# FT2328Breakout.net
KiCad netlist of a schematic drawn in EAGLE
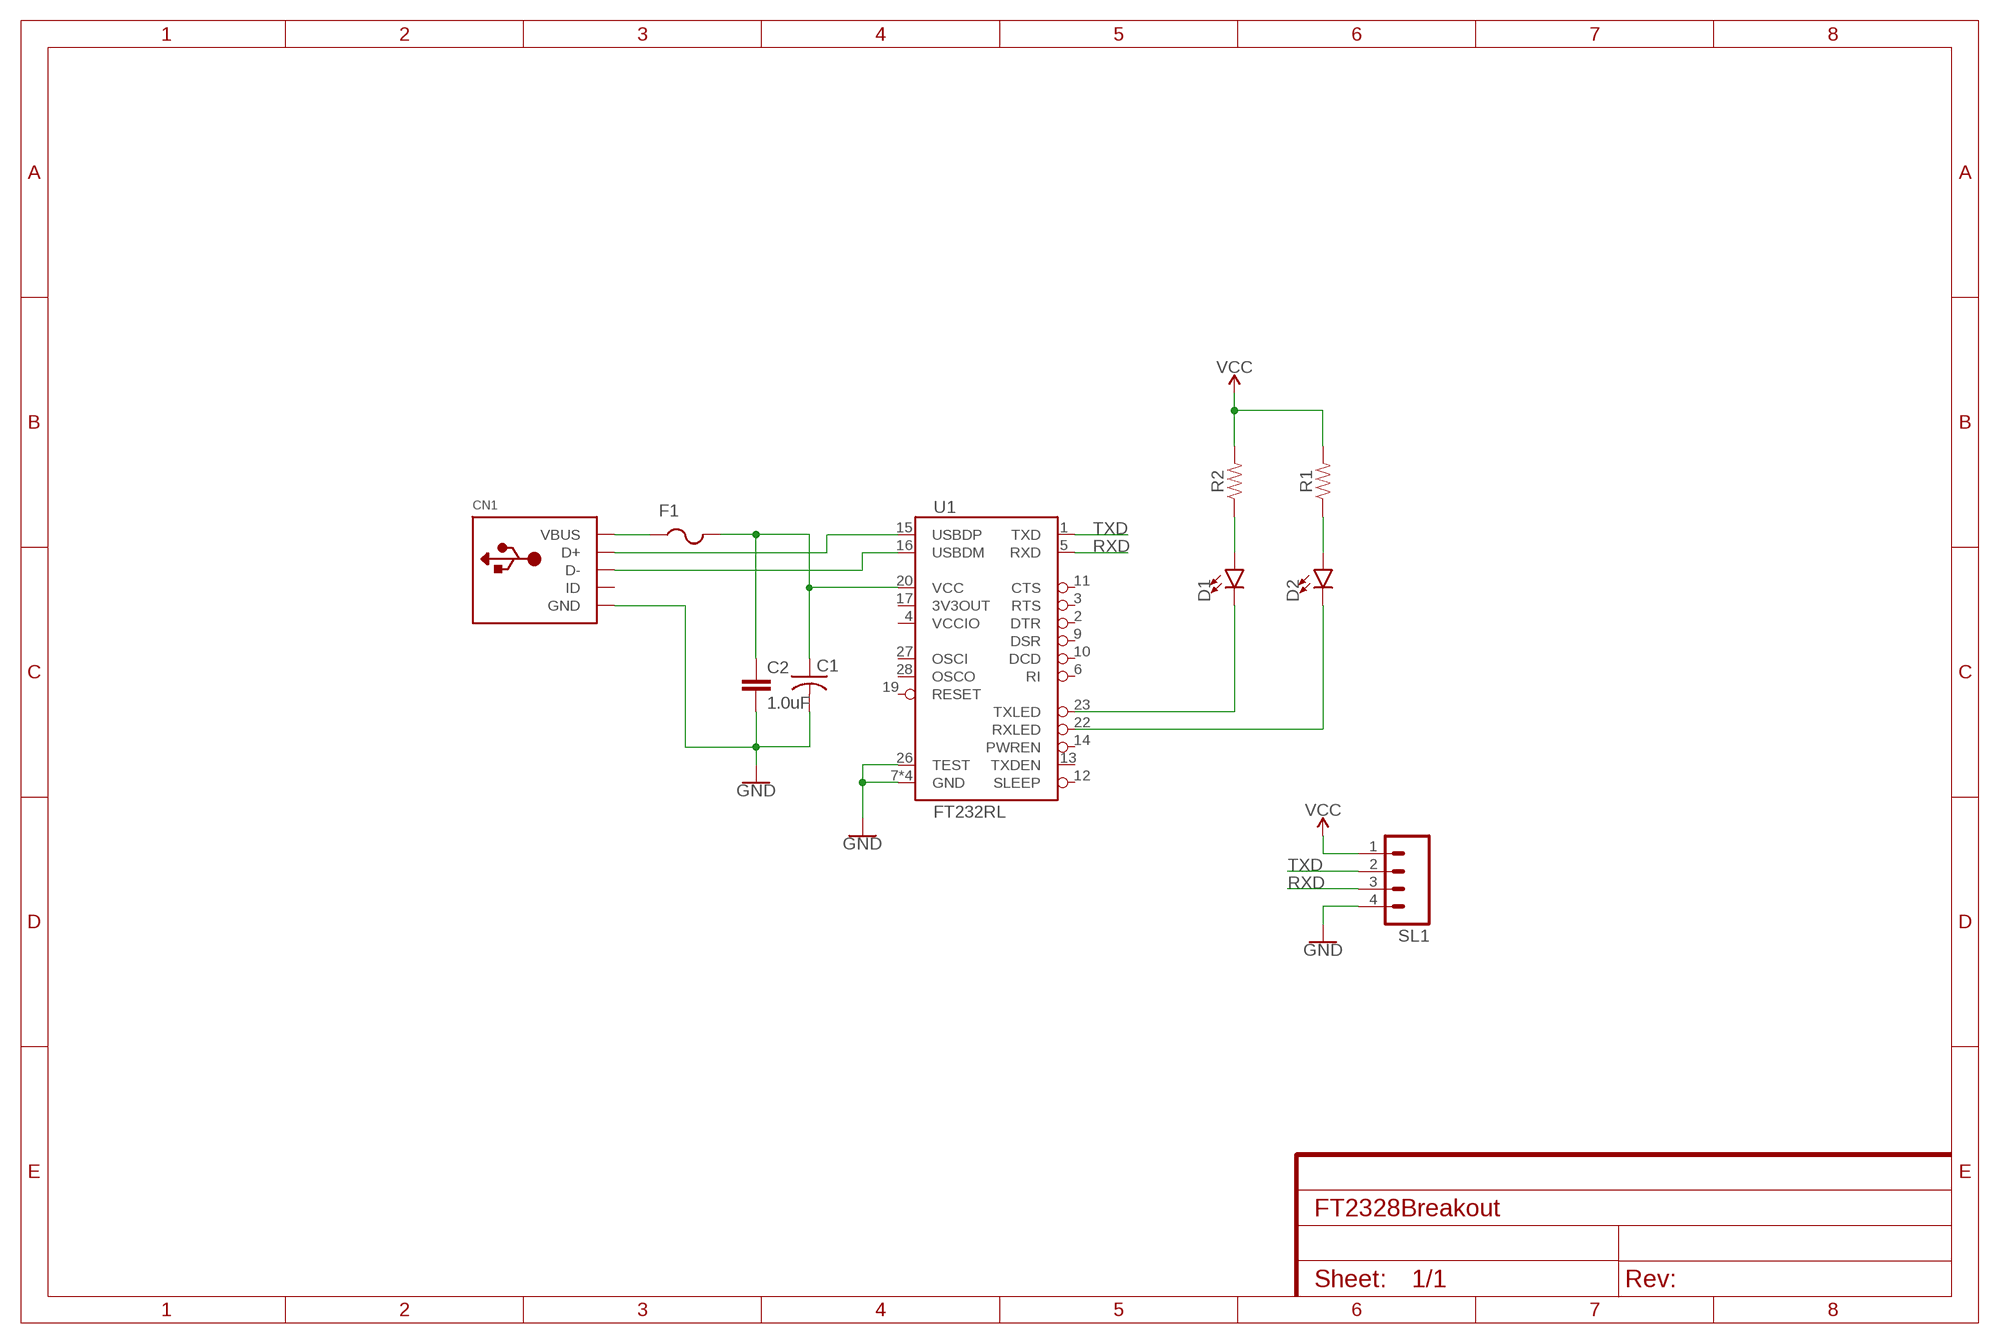
[diagram p0: schematic, sheet 1]

(export (version "E")
  (design (tool "Eeschema 10.0.6"))
  (components
    (comp (ref "C1")
      (value "C-USC1206")
      (footprint "eagle-import:C1206")
      (libsource (lib "eagle-import") (part "C-USC1206"))
    )
    (comp (ref "C2")
      (value "1.0uF")
      (footprint "eagle-import:1206")
      (libsource (lib "eagle-import") (part "1.0UF-1206-50V-10%"))
    )
    (comp (ref "CN1")
      (value "USBMINIB")
      (footprint "eagle-import:USB-MINIB")
      (libsource (lib "eagle-import") (part "USBMINIB"))
    )
    (comp (ref "D1")
      (value "LED1206")
      (footprint "eagle-import:LED-1206")
      (libsource (lib "eagle-import") (part "LED1206"))
    )
    (comp (ref "D2")
      (value "LED1206")
      (footprint "eagle-import:LED-1206")
      (libsource (lib "eagle-import") (part "LED1206"))
    )
    (comp (ref "F1")
      (value "PTCFUSE-1206")
      (footprint "eagle-import:R1206")
      (libsource (lib "eagle-import") (part "PTCFUSE-1206"))
    )
    (comp (ref "R1")
      (value "RESISTOR1206")
      (footprint "eagle-import:1206")
      (libsource (lib "eagle-import") (part "RESISTOR1206"))
    )
    (comp (ref "R2")
      (value "RESISTOR1206")
      (footprint "eagle-import:1206")
      (libsource (lib "eagle-import") (part "RESISTOR1206"))
    )
    (comp (ref "SL1")
      (value "M04")
      (footprint "eagle-import:04P")
      (libsource (lib "eagle-import") (part "M04"))
    )
    (comp (ref "U1")
      (value "FT232RL")
      (footprint "eagle-import:SSOP28DB")
      (libsource (lib "eagle-import") (part "FT232RLSSOP"))
    )
  )
  (nets
    (net (code "1") (name "/RXD") (class "Default")
      (node (ref "SL1") (pin "3") (pinfunction "3_3") (pintype "passive"))
      (node (ref "U1") (pin "5") (pinfunction "RXD_5") (pintype "input"))
    )
    (net (code "2") (name "/TXD") (class "Default")
      (node (ref "SL1") (pin "2") (pinfunction "2_2") (pintype "passive"))
      (node (ref "U1") (pin "1") (pinfunction "TXD_1") (pintype "output"))
    )
    (net (code "3") (name "/VCCIO") (class "Default")
      (node (ref "U1") (pin "4") (pinfunction "VCCIO_4") (pintype "power_in"))
    )
    (net (code "4") (name "GND") (class "Default")
      (node (ref "C1") (pin "2") (pinfunction "2_2") (pintype "passive"))
      (node (ref "C2") (pin "2") (pinfunction "2_2") (pintype "passive"))
      (node (ref "CN1") (pin "GND") (pinfunction "GND_GND") (pintype "power_in"))
      (node (ref "SL1") (pin "4") (pinfunction "4_4") (pintype "passive"))
      (node (ref "U1") (pin "18") (pinfunction "GND_18") (pintype "power_in"))
      (node (ref "U1") (pin "21") (pinfunction "GND_21") (pintype "power_in"))
      (node (ref "U1") (pin "25") (pinfunction "GND_25") (pintype "power_in"))
      (node (ref "U1") (pin "26") (pinfunction "TEST_26") (pintype "input"))
      (node (ref "U1") (pin "7") (pinfunction "GND_7") (pintype "power_in"))
    )
    (net (code "5") (name "Net-(CN1-PadVBUS)") (class "Default")
      (node (ref "CN1") (pin "VBUS") (pinfunction "VBUS_VBUS") (pintype "power_in"))
      (node (ref "F1") (pin "1") (pinfunction "1_1") (pintype "passive"))
    )
    (net (code "6") (name "Net-(D1-PadA)") (class "Default")
      (node (ref "D1") (pin "A") (pinfunction "A_A") (pintype "passive"))
      (node (ref "R2") (pin "1") (pinfunction "1_1") (pintype "passive"))
    )
    (net (code "7") (name "Net-(D2-PadA)") (class "Default")
      (node (ref "D2") (pin "A") (pinfunction "A_A") (pintype "passive"))
      (node (ref "R1") (pin "1") (pinfunction "1_1") (pintype "passive"))
    )
    (net (code "8") (name "Net-(U1-RXLED)") (class "Default")
      (node (ref "D2") (pin "C") (pinfunction "C_C") (pintype "passive"))
      (node (ref "U1") (pin "22") (pinfunction "RXLED_22") (pintype "input"))
    )
    (net (code "9") (name "Net-(U1-TXLED)") (class "Default")
      (node (ref "D1") (pin "C") (pinfunction "C_C") (pintype "passive"))
      (node (ref "U1") (pin "23") (pinfunction "TXLED_23") (pintype "input"))
    )
    (net (code "10") (name "Net-(U1-USBDM)") (class "Default")
      (node (ref "CN1") (pin "D-") (pinfunction "D-_D-") (pintype "bidirectional"))
      (node (ref "U1") (pin "16") (pinfunction "USBDM_16") (pintype "bidirectional"))
    )
    (net (code "11") (name "Net-(U1-USBDP)") (class "Default")
      (node (ref "CN1") (pin "D+") (pinfunction "D+_D+") (pintype "bidirectional"))
      (node (ref "U1") (pin "15") (pinfunction "USBDP_15") (pintype "bidirectional"))
    )
    (net (code "12") (name "Net-(U1-VCC)") (class "Default")
      (node (ref "C1") (pin "1") (pinfunction "1_1") (pintype "passive"))
      (node (ref "C2") (pin "1") (pinfunction "1_1") (pintype "passive"))
      (node (ref "F1") (pin "2") (pinfunction "2_2") (pintype "passive"))
      (node (ref "U1") (pin "20") (pinfunction "VCC_20") (pintype "power_in"))
    )
    (net (code "13") (name "VCC") (class "Default")
      (node (ref "R1") (pin "2") (pinfunction "2_2") (pintype "passive"))
      (node (ref "R2") (pin "2") (pinfunction "2_2") (pintype "passive"))
      (node (ref "SL1") (pin "1") (pinfunction "1_1") (pintype "passive"))
    )
    (net (code "14") (name "unconnected-(CN1-PadID)") (class "Default")
      (node (ref "CN1") (pin "ID") (pinfunction "ID_ID") (pintype "bidirectional"))
    )
    (net (code "15") (name "unconnected-(U1-3V3OUT-Pad17)") (class "Default")
      (node (ref "U1") (pin "17") (pinfunction "3V3OUT_17") (pintype "output"))
    )
    (net (code "16") (name "unconnected-(U1-CTS-Pad11)") (class "Default")
      (node (ref "U1") (pin "11") (pinfunction "CTS_11") (pintype "input"))
    )
    (net (code "17") (name "unconnected-(U1-DCD-Pad10)") (class "Default")
      (node (ref "U1") (pin "10") (pinfunction "DCD_10") (pintype "input"))
    )
    (net (code "18") (name "unconnected-(U1-DSR-Pad9)") (class "Default")
      (node (ref "U1") (pin "9") (pinfunction "DSR_9") (pintype "input"))
    )
    (net (code "19") (name "unconnected-(U1-DTR-Pad2)") (class "Default")
      (node (ref "U1") (pin "2") (pinfunction "DTR_2") (pintype "output"))
    )
    (net (code "20") (name "unconnected-(U1-OSCI-Pad27)") (class "Default")
      (node (ref "U1") (pin "27") (pinfunction "OSCI_27") (pintype "input"))
    )
    (net (code "21") (name "unconnected-(U1-OSCO-Pad28)") (class "Default")
      (node (ref "U1") (pin "28") (pinfunction "OSCO_28") (pintype "output"))
    )
    (net (code "22") (name "unconnected-(U1-PWREN-Pad14)") (class "Default")
      (node (ref "U1") (pin "14") (pinfunction "PWREN_14") (pintype "input"))
    )
    (net (code "23") (name "unconnected-(U1-RESET-Pad19)") (class "Default")
      (node (ref "U1") (pin "19") (pinfunction "RESET_19") (pintype "input"))
    )
    (net (code "24") (name "unconnected-(U1-RI-Pad6)") (class "Default")
      (node (ref "U1") (pin "6") (pinfunction "RI_6") (pintype "input"))
    )
    (net (code "25") (name "unconnected-(U1-RTS-Pad3)") (class "Default")
      (node (ref "U1") (pin "3") (pinfunction "RTS_3") (pintype "output"))
    )
    (net (code "26") (name "unconnected-(U1-SLEEP-Pad12)") (class "Default")
      (node (ref "U1") (pin "12") (pinfunction "SLEEP_12") (pintype "input"))
    )
    (net (code "27") (name "unconnected-(U1-TXDEN-Pad13)") (class "Default")
      (node (ref "U1") (pin "13") (pinfunction "TXDEN_13") (pintype "input"))
    )
  )
)
